# OTP.net
KiCad netlist of a schematic drawn in Altium Designer
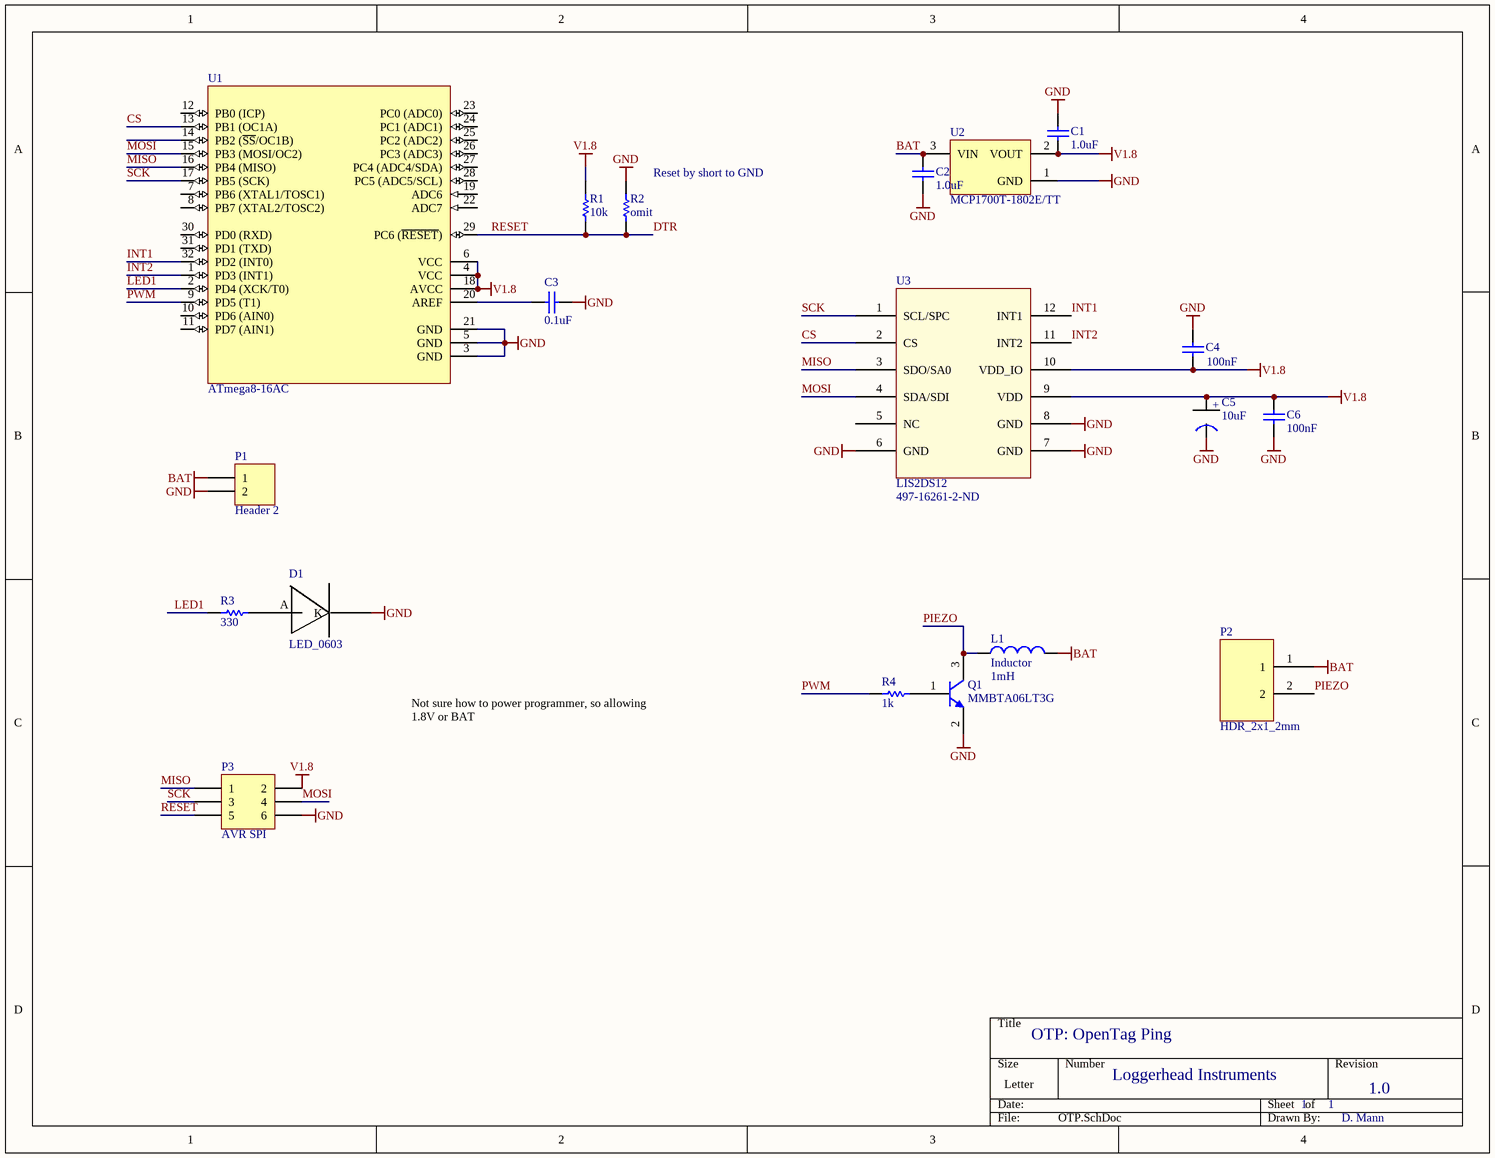
[diagram p0: OTP.SchDoc]

(export (version "E")
  (design (tool "Eeschema 10.0.6"))
  (components
    (comp (ref "C1")
      (value "1.0uF")
      (footprint "0402")
      (description "Ceramic Chip Capacitor - Standard")
      (fields (field (name "PUBLISHER") "Altium Limited"))
      (libsource (lib "KEMET Chip Capacitor") (part "C0402"))
    )
    (comp (ref "C2")
      (value "1.0uF")
      (footprint "0402")
      (description "Ceramic Chip Capacitor - Standard")
      (fields (field (name "PUBLISHER") "Altium Limited"))
      (libsource (lib "KEMET Chip Capacitor") (part "C0402"))
    )
    (comp (ref "C3")
      (value "0.1uF")
      (footprint "0402")
      (description "Ceramic Chip Capacitor - Standard")
      (fields (field (name "PUBLISHER") "Altium Limited"))
      (libsource (lib "KEMET Chip Capacitor") (part "C0402"))
    )
    (comp (ref "C4")
      (value "100nF")
      (footprint "0402")
      (description "Ceramic Chip Capacitor - Standard")
      (fields (field (name "PUBLISHER") "Altium Limited"))
      (libsource (lib "KEMET Chip Capacitor") (part "C0402"))
    )
    (comp (ref "C5") (value "10uF") (footprint "Tant0805") (libsource (lib "Loggerhead") (part "Tant0805")))
    (comp (ref "C6")
      (value "100nF")
      (footprint "0402")
      (description "Ceramic Chip Capacitor - Standard")
      (fields (field (name "PUBLISHER") "Altium Limited"))
      (libsource (lib "KEMET Chip Capacitor") (part "C0402"))
    )
    (comp (ref "D1")
      (value "LED_0603")
      (footprint "Diode0603")
      (libsource (lib "Loggerhead") (part "LED_0603"))
    )
    (comp (ref "L1")
      (value "Inductor")
      (footprint "INDC3216")
      (fields (field (name "ALTIUM_VALUE") "1mH") (field (name "PUBLISHER") "Altium Limited"))
      (libsource (lib "Miscellaneous Devices") (part "Inductor"))
    )
    (comp (ref "P1")
      (value "Header 2")
      (footprint "HDR1X2")
      (description "Header, 2-Pin")
      (fields (field (name "PUBLISHER") "Altium Limited"))
      (libsource (lib "Miscellaneous Connectors") (part "Header 2"))
    )
    (comp (ref "P2")
      (value "HDR_2x1_2mm")
      (footprint "HDR_2x1_2mm")
      (libsource (lib "Loggerhead") (part "HDR_2x1_2mm"))
    )
    (comp (ref "P3")
      (value "AVR SPI")
      (footprint "HDR2X3")
      (description "Header, 3-Pin, Dual row")
      (fields (field (name "PUBLISHER") "Altium Limited"))
      (libsource (lib "Miscellaneous Connectors") (part "Header 3X2"))
    )
    (comp (ref "Q1")
      (value "MMBTA06LT3G")
      (footprint "ONSC-SOT-23-3-318-08_V")
      (description "Driver Transistor, NPN Silicon, 3-Pin SOT-23, Pb-Free, Tape and Reel")
      (fields (field (name "MANUFACTURER") "On Semiconductor"))
      (libsource (lib "ON Semi General Purpose Transistors") (part "MMBTA06LT3G"))
    )
    (comp (ref "R1")
      (value "10k")
      (footprint "3-0603")
      (fields (field (name "PUBLISHER") "Altium Limited"))
      (libsource (lib "Panasonic Resistor") (part "ERJ3RK"))
    )
    (comp (ref "R2")
      (value "omit")
      (footprint "3-0603")
      (fields (field (name "PUBLISHER") "Altium Limited"))
      (libsource (lib "Panasonic Resistor") (part "ERJ3RK"))
    )
    (comp (ref "R3")
      (value "330")
      (footprint "3-0603")
      (fields (field (name "PUBLISHER") "Altium Limited"))
      (libsource (lib "Panasonic Resistor") (part "ERJ3RK"))
    )
    (comp (ref "R4")
      (value "1k")
      (footprint "3-0603")
      (fields (field (name "PUBLISHER") "Altium Limited"))
      (libsource (lib "Panasonic Resistor") (part "ERJ3RK"))
    )
    (comp (ref "U1")
      (value "ATmega8-16AC")
      (footprint "32M1-A_M")
      (description "8-Bit AVR Microcontroller with 8K Bytes of In-System Programmable Flash Memory")
      (fields (field (name "PUBLISHER") "Altium Limited"))
      (libsource (lib "Atmel Microcontroller 8-Bit AVR") (part "ATmega8-16AC"))
    )
    (comp (ref "U2")
      (value "MCP1700T-1802E/TT")
      (footprint "SOT-23-TT3_N")
      (description "Low Quiescent Current LDO, 3-Pin SOT-23, Extended Temperature, Tape and Reel")
      (fields (field (name "MANUFACTURER") "Microchip"))
      (libsource (lib "Microchip Power Management Line Regulator") (part "MCP1700T-1802E/TT"))
    )
    (comp (ref "U3")
      (value "LIS2DS12")
      (footprint "LGA-12")
      (fields (field (name "SUPPLIER PART NUMBER 1") "497-16261-2-ND"))
      (libsource (lib "Loggerhead") (part "LIS2DS12"))
    )
  )
  (nets
    (net (code "1") (name "/CS") (class "Default")
      (node (ref "U1") (pin "13") (pinfunction "PB1_(OC1A)_13") (pintype "bidirectional"))
      (node (ref "U3") (pin "2") (pinfunction "CS_2") (pintype "passive"))
    )
    (net (code "2") (name "/DTR") (class "Default")
      (node (ref "P3") (pin "5") (pinfunction "5_5") (pintype "passive"))
      (node (ref "R1") (pin "1") (pinfunction "1_1") (pintype "passive"))
      (node (ref "R2") (pin "1") (pinfunction "1_1") (pintype "passive"))
      (node (ref "U1") (pin "29") (pinfunction "PC6_(~{RESET})_29") (pintype "bidirectional"))
    )
    (net (code "3") (name "/INT1") (class "Default")
      (node (ref "U1") (pin "32") (pinfunction "PD2_(INT0)_32") (pintype "bidirectional"))
      (node (ref "U3") (pin "12") (pinfunction "INT1_12") (pintype "passive"))
    )
    (net (code "4") (name "/INT2") (class "Default")
      (node (ref "U1") (pin "1") (pinfunction "PD3_(INT1)_1") (pintype "bidirectional"))
      (node (ref "U3") (pin "11") (pinfunction "INT2_11") (pintype "passive"))
    )
    (net (code "5") (name "/LED1") (class "Default")
      (node (ref "R3") (pin "1") (pinfunction "1_1") (pintype "passive"))
      (node (ref "U1") (pin "2") (pinfunction "PD4_(XCK/T0)_2") (pintype "bidirectional"))
    )
    (net (code "6") (name "/MISO") (class "Default")
      (node (ref "P3") (pin "1") (pinfunction "1_1") (pintype "passive"))
      (node (ref "U1") (pin "16") (pinfunction "PB4_(MISO)_16") (pintype "bidirectional"))
      (node (ref "U3") (pin "3") (pinfunction "SDO/SA0_3") (pintype "passive"))
    )
    (net (code "7") (name "/MOSI") (class "Default")
      (node (ref "P3") (pin "4") (pinfunction "4_4") (pintype "passive"))
      (node (ref "U1") (pin "15") (pinfunction "PB3_(MOSI/OC2)_15") (pintype "bidirectional"))
      (node (ref "U3") (pin "4") (pinfunction "SDA/SDI_4") (pintype "passive"))
    )
    (net (code "8") (name "/PIEZO") (class "Default")
      (node (ref "L1") (pin "1") (pinfunction "1_1") (pintype "passive"))
      (node (ref "P2") (pin "2") (pinfunction "2_2") (pintype "passive"))
      (node (ref "Q1") (pin "3") (pinfunction "C_3") (pintype "passive"))
    )
    (net (code "9") (name "/PWM") (class "Default")
      (node (ref "R4") (pin "1") (pinfunction "1_1") (pintype "passive"))
      (node (ref "U1") (pin "9") (pinfunction "PD5_(T1)_9") (pintype "bidirectional"))
    )
    (net (code "10") (name "/SCK") (class "Default")
      (node (ref "P3") (pin "3") (pinfunction "3_3") (pintype "passive"))
      (node (ref "U1") (pin "17") (pinfunction "PB5_(SCK)_17") (pintype "bidirectional"))
      (node (ref "U3") (pin "1") (pinfunction "SCL/SPC_1") (pintype "passive"))
    )
    (net (code "11") (name "BAT") (class "Default")
      (node (ref "C2") (pin "1") (pinfunction "1_1") (pintype "passive"))
      (node (ref "L1") (pin "2") (pinfunction "2_2") (pintype "passive"))
      (node (ref "P1") (pin "1") (pinfunction "1_1") (pintype "passive"))
      (node (ref "P2") (pin "1") (pinfunction "1_1") (pintype "passive"))
      (node (ref "U2") (pin "3") (pinfunction "VIN_3") (pintype "power_in"))
    )
    (net (code "12") (name "GND") (class "Default")
      (node (ref "C1") (pin "2") (pinfunction "2_2") (pintype "passive"))
      (node (ref "C2") (pin "2") (pinfunction "2_2") (pintype "passive"))
      (node (ref "C3") (pin "2") (pinfunction "2_2") (pintype "passive"))
      (node (ref "C4") (pin "2") (pinfunction "2_2") (pintype "passive"))
      (node (ref "C5") (pin "1") (pinfunction "GND_1") (pintype "passive"))
      (node (ref "C6") (pin "2") (pinfunction "2_2") (pintype "passive"))
      (node (ref "D1") (pin "K") (pinfunction "K_K") (pintype "passive"))
      (node (ref "P1") (pin "2") (pinfunction "2_2") (pintype "passive"))
      (node (ref "P3") (pin "6") (pinfunction "6_6") (pintype "passive"))
      (node (ref "Q1") (pin "2") (pinfunction "E_2") (pintype "passive"))
      (node (ref "R2") (pin "2") (pinfunction "2_2") (pintype "passive"))
      (node (ref "U1") (pin "21") (pinfunction "GND_21") (pintype "power_in"))
      (node (ref "U1") (pin "3") (pinfunction "GND_3") (pintype "power_in"))
      (node (ref "U1") (pin "5") (pinfunction "GND_5") (pintype "power_in"))
      (node (ref "U2") (pin "1") (pinfunction "GND_1") (pintype "power_in"))
      (node (ref "U3") (pin "6") (pinfunction "GND_6") (pintype "passive"))
      (node (ref "U3") (pin "7") (pinfunction "GND_7") (pintype "passive"))
      (node (ref "U3") (pin "8") (pinfunction "GND_8") (pintype "passive"))
    )
    (net (code "13") (name "Net-(D1-PadA)") (class "Default")
      (node (ref "D1") (pin "A") (pinfunction "A_A") (pintype "passive"))
      (node (ref "R3") (pin "2") (pinfunction "2_2") (pintype "passive"))
    )
    (net (code "14") (name "Net-(Q1-B)") (class "Default")
      (node (ref "Q1") (pin "1") (pinfunction "B_1") (pintype "passive"))
      (node (ref "R4") (pin "2") (pinfunction "2_2") (pintype "passive"))
    )
    (net (code "15") (name "Net-(U1-AREF)") (class "Default")
      (node (ref "C3") (pin "1") (pinfunction "1_1") (pintype "passive"))
      (node (ref "U1") (pin "20") (pinfunction "AREF_20") (pintype "passive"))
    )
    (net (code "16") (name "V1.8") (class "Default")
      (node (ref "C1") (pin "1") (pinfunction "1_1") (pintype "passive"))
      (node (ref "C4") (pin "1") (pinfunction "1_1") (pintype "passive"))
      (node (ref "C5") (pin "2") (pinfunction "+_2") (pintype "passive"))
      (node (ref "C6") (pin "1") (pinfunction "1_1") (pintype "passive"))
      (node (ref "P3") (pin "2") (pinfunction "2_2") (pintype "passive"))
      (node (ref "R1") (pin "2") (pinfunction "2_2") (pintype "passive"))
      (node (ref "U1") (pin "18") (pinfunction "AVCC_18") (pintype "power_in"))
      (node (ref "U1") (pin "4") (pinfunction "VCC_4") (pintype "power_in"))
      (node (ref "U1") (pin "6") (pinfunction "VCC_6") (pintype "power_in"))
      (node (ref "U2") (pin "2") (pinfunction "VOUT_2") (pintype "power_in"))
      (node (ref "U3") (pin "10") (pinfunction "VDD_IO_10") (pintype "passive"))
      (node (ref "U3") (pin "9") (pinfunction "VDD_9") (pintype "passive"))
    )
    (net (code "17") (name "unconnected-(U1-ADC6-Pad19)") (class "Default")
      (node (ref "U1") (pin "19") (pinfunction "ADC6_19") (pintype "input"))
    )
    (net (code "18") (name "unconnected-(U1-ADC7-Pad22)") (class "Default")
      (node (ref "U1") (pin "22") (pinfunction "ADC7_22") (pintype "input"))
    )
    (net (code "19") (name "unconnected-(U1-PB0_(ICP)-Pad12)") (class "Default")
      (node (ref "U1") (pin "12") (pinfunction "PB0_(ICP)_12") (pintype "bidirectional"))
    )
    (net (code "20") (name "unconnected-(U1-PB2_(~{SS}{slash}OC1B)-Pad14)") (class "Default")
      (node (ref "U1") (pin "14") (pinfunction "PB2_(~{SS}/OC1B)_14") (pintype "bidirectional"))
    )
    (net (code "21") (name "unconnected-(U1-PB6_(XTAL1{slash}TOSC1)-Pad7)") (class "Default")
      (node (ref "U1") (pin "7") (pinfunction "PB6_(XTAL1/TOSC1)_7") (pintype "bidirectional"))
    )
    (net (code "22") (name "unconnected-(U1-PB7_(XTAL2{slash}TOSC2)-Pad8)") (class "Default")
      (node (ref "U1") (pin "8") (pinfunction "PB7_(XTAL2/TOSC2)_8") (pintype "bidirectional"))
    )
    (net (code "23") (name "unconnected-(U1-PC0_(ADC0)-Pad23)") (class "Default")
      (node (ref "U1") (pin "23") (pinfunction "PC0_(ADC0)_23") (pintype "bidirectional"))
    )
    (net (code "24") (name "unconnected-(U1-PC1_(ADC1)-Pad24)") (class "Default")
      (node (ref "U1") (pin "24") (pinfunction "PC1_(ADC1)_24") (pintype "bidirectional"))
    )
    (net (code "25") (name "unconnected-(U1-PC2_(ADC2)-Pad25)") (class "Default")
      (node (ref "U1") (pin "25") (pinfunction "PC2_(ADC2)_25") (pintype "bidirectional"))
    )
    (net (code "26") (name "unconnected-(U1-PC3_(ADC3)-Pad26)") (class "Default")
      (node (ref "U1") (pin "26") (pinfunction "PC3_(ADC3)_26") (pintype "bidirectional"))
    )
    (net (code "27") (name "unconnected-(U1-PC4_(ADC4{slash}SDA)-Pad27)") (class "Default")
      (node (ref "U1") (pin "27") (pinfunction "PC4_(ADC4/SDA)_27") (pintype "bidirectional"))
    )
    (net (code "28") (name "unconnected-(U1-PC5_(ADC5{slash}SCL)-Pad28)") (class "Default")
      (node (ref "U1") (pin "28") (pinfunction "PC5_(ADC5/SCL)_28") (pintype "bidirectional"))
    )
    (net (code "29") (name "unconnected-(U1-PD0_(RXD)-Pad30)") (class "Default")
      (node (ref "U1") (pin "30") (pinfunction "PD0_(RXD)_30") (pintype "bidirectional"))
    )
    (net (code "30") (name "unconnected-(U1-PD1_(TXD)-Pad31)") (class "Default")
      (node (ref "U1") (pin "31") (pinfunction "PD1_(TXD)_31") (pintype "bidirectional"))
    )
    (net (code "31") (name "unconnected-(U1-PD6_(AIN0)-Pad10)") (class "Default")
      (node (ref "U1") (pin "10") (pinfunction "PD6_(AIN0)_10") (pintype "bidirectional"))
    )
    (net (code "32") (name "unconnected-(U1-PD7_(AIN1)-Pad11)") (class "Default")
      (node (ref "U1") (pin "11") (pinfunction "PD7_(AIN1)_11") (pintype "bidirectional"))
    )
    (net (code "33") (name "unconnected-(U3-NC-Pad5)") (class "Default")
      (node (ref "U3") (pin "5") (pinfunction "NC_5") (pintype "passive"))
    )
  )
)
